# LightSensor_S002A.net
KiCad netlist of a schematic drawn in EAGLE
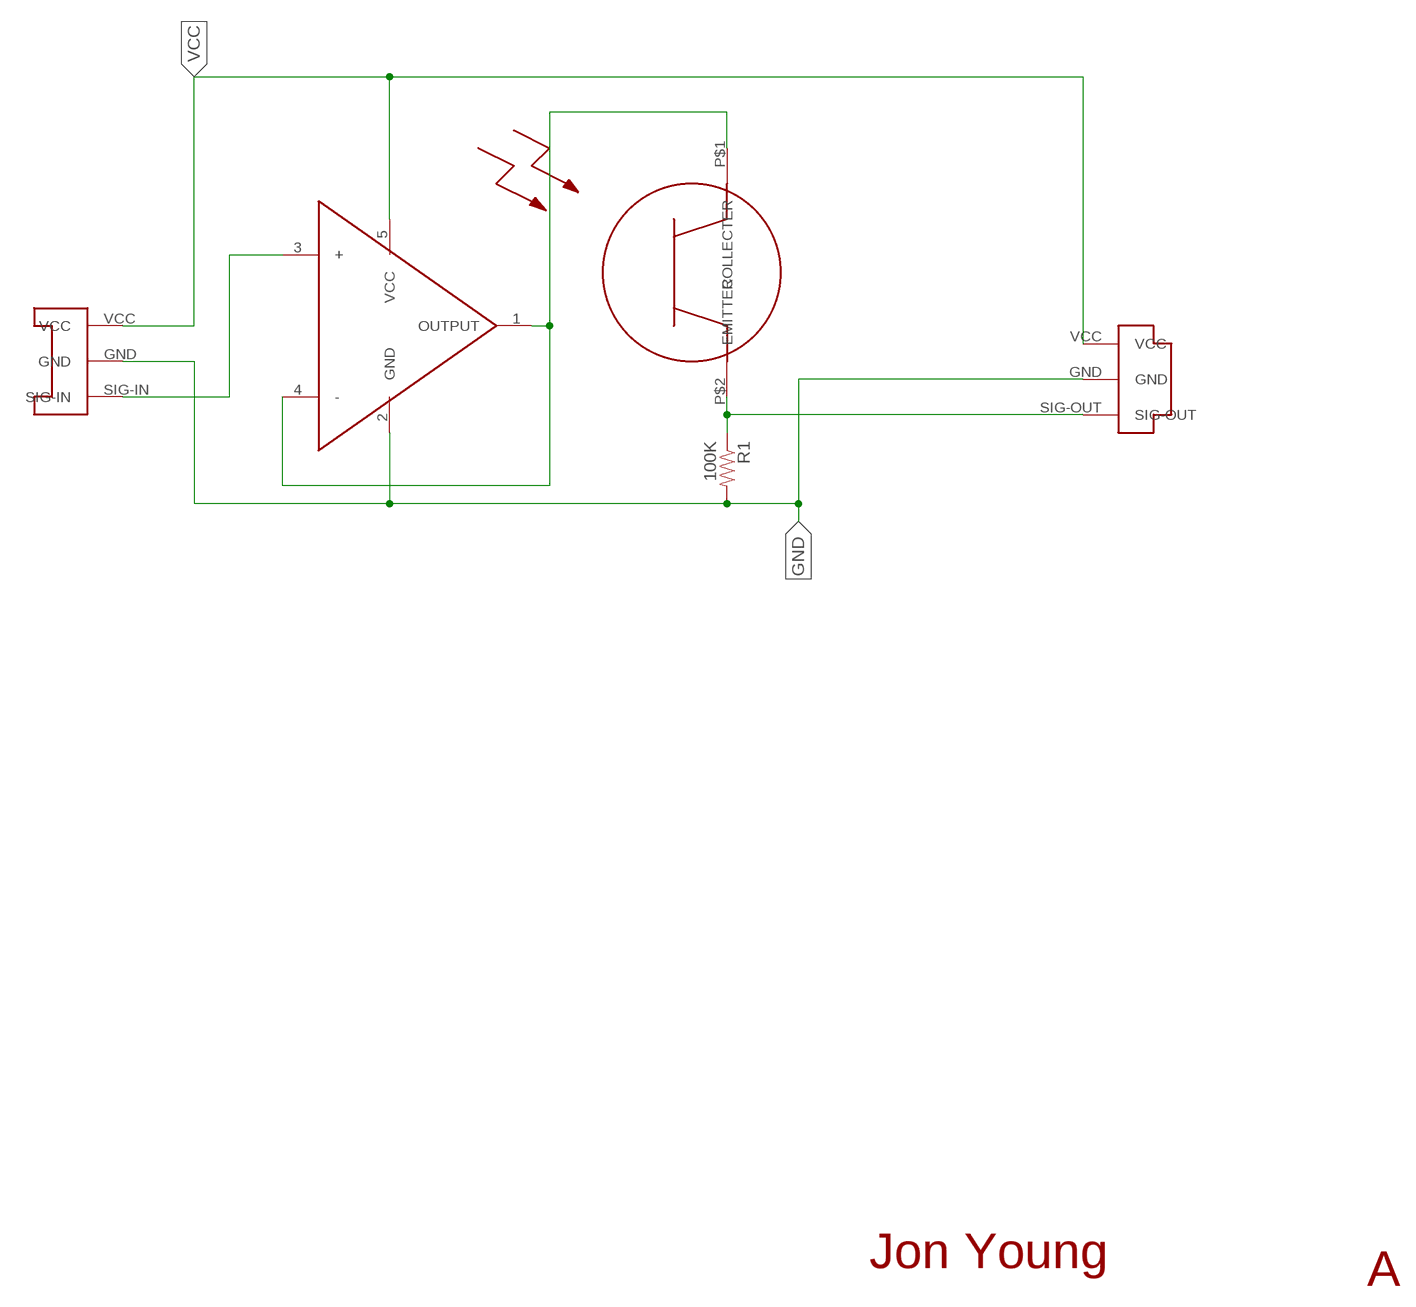
[diagram p0: schematic, sheet 1]

(export (version "E")
  (design (tool "Eeschema 10.0.6"))
  (components
    (comp (ref "R1")
      (value "100K")
      (footprint "eagle-import:0603-RES")
      (libsource (lib "eagle-import") (part "RESISTOR0603"))
    )
    (comp (ref "U$1")
      (value "CONN-PLUG-3POS-3MM")
      (footprint "eagle-import:PLUG-3POS-3MM-SMD")
      (libsource (lib "eagle-import") (part "CONN-PLUG-3POS-3MM"))
    )
    (comp (ref "U$2")
      (value "CONN-SOCKET-3POS-3MM")
      (footprint "eagle-import:SOCKET-3POS-3MM-SMD")
      (libsource (lib "eagle-import") (part "CONN-SOCKET-3POS-3MM"))
    )
    (comp (ref "U$3")
      (value "OPAMP-MCP6001SC70-5")
      (footprint "eagle-import:SC70")
      (libsource (lib "eagle-import") (part "OPAMP-MCP6001SC70-5"))
    )
    (comp (ref "U$4")
      (value "AMBIENT-LIGHT-SENSOR-DIODE")
      (footprint "eagle-import:AMBIENT-LIGHT-SENSOR-PT19")
      (libsource (lib "eagle-import") (part "AMBIENT-LIGHT-SENSOR-DIODE"))
    )
  )
  (nets
    (net (code "1") (name "GND") (class "Default")
      (node (ref "R1") (pin "2") (pinfunction "2_2") (pintype "passive"))
      (node (ref "U$1") (pin "GND") (pinfunction "GND_GND") (pintype "power_in"))
      (node (ref "U$2") (pin "GND") (pinfunction "GND_GND") (pintype "power_in"))
      (node (ref "U$3") (pin "2") (pinfunction "GND_2") (pintype "power_in"))
    )
    (net (code "2") (name "Net-(U$3-+)") (class "Default")
      (node (ref "U$2") (pin "SIG-IN") (pinfunction "SIG-IN_SIG-IN") (pintype "bidirectional"))
      (node (ref "U$3") (pin "3") (pinfunction "+_3") (pintype "input"))
    )
    (net (code "3") (name "Net-(U$3--)") (class "Default")
      (node (ref "U$3") (pin "1") (pinfunction "OUTPUT_1") (pintype "output"))
      (node (ref "U$3") (pin "4") (pinfunction "-_4") (pintype "input"))
      (node (ref "U$4") (pin "P$1") (pinfunction "COLLECTER_P$1") (pintype "input"))
    )
    (net (code "4") (name "Net-(U$4-EMITTER)") (class "Default")
      (node (ref "R1") (pin "1") (pinfunction "1_1") (pintype "passive"))
      (node (ref "U$1") (pin "SIG-OUT") (pinfunction "SIG-OUT_SIG-OUT") (pintype "bidirectional"))
      (node (ref "U$4") (pin "P$2") (pinfunction "EMITTER_P$2") (pintype "output"))
    )
    (net (code "5") (name "VCC") (class "Default")
      (node (ref "U$1") (pin "VCC") (pinfunction "VCC_VCC") (pintype "power_in"))
      (node (ref "U$2") (pin "VCC") (pinfunction "VCC_VCC") (pintype "power_in"))
      (node (ref "U$3") (pin "5") (pinfunction "VCC_5") (pintype "power_in"))
    )
  )
)
